# PROC099A_PMIC_Reference.net
KiCad netlist of a schematic drawn in Altium Designer
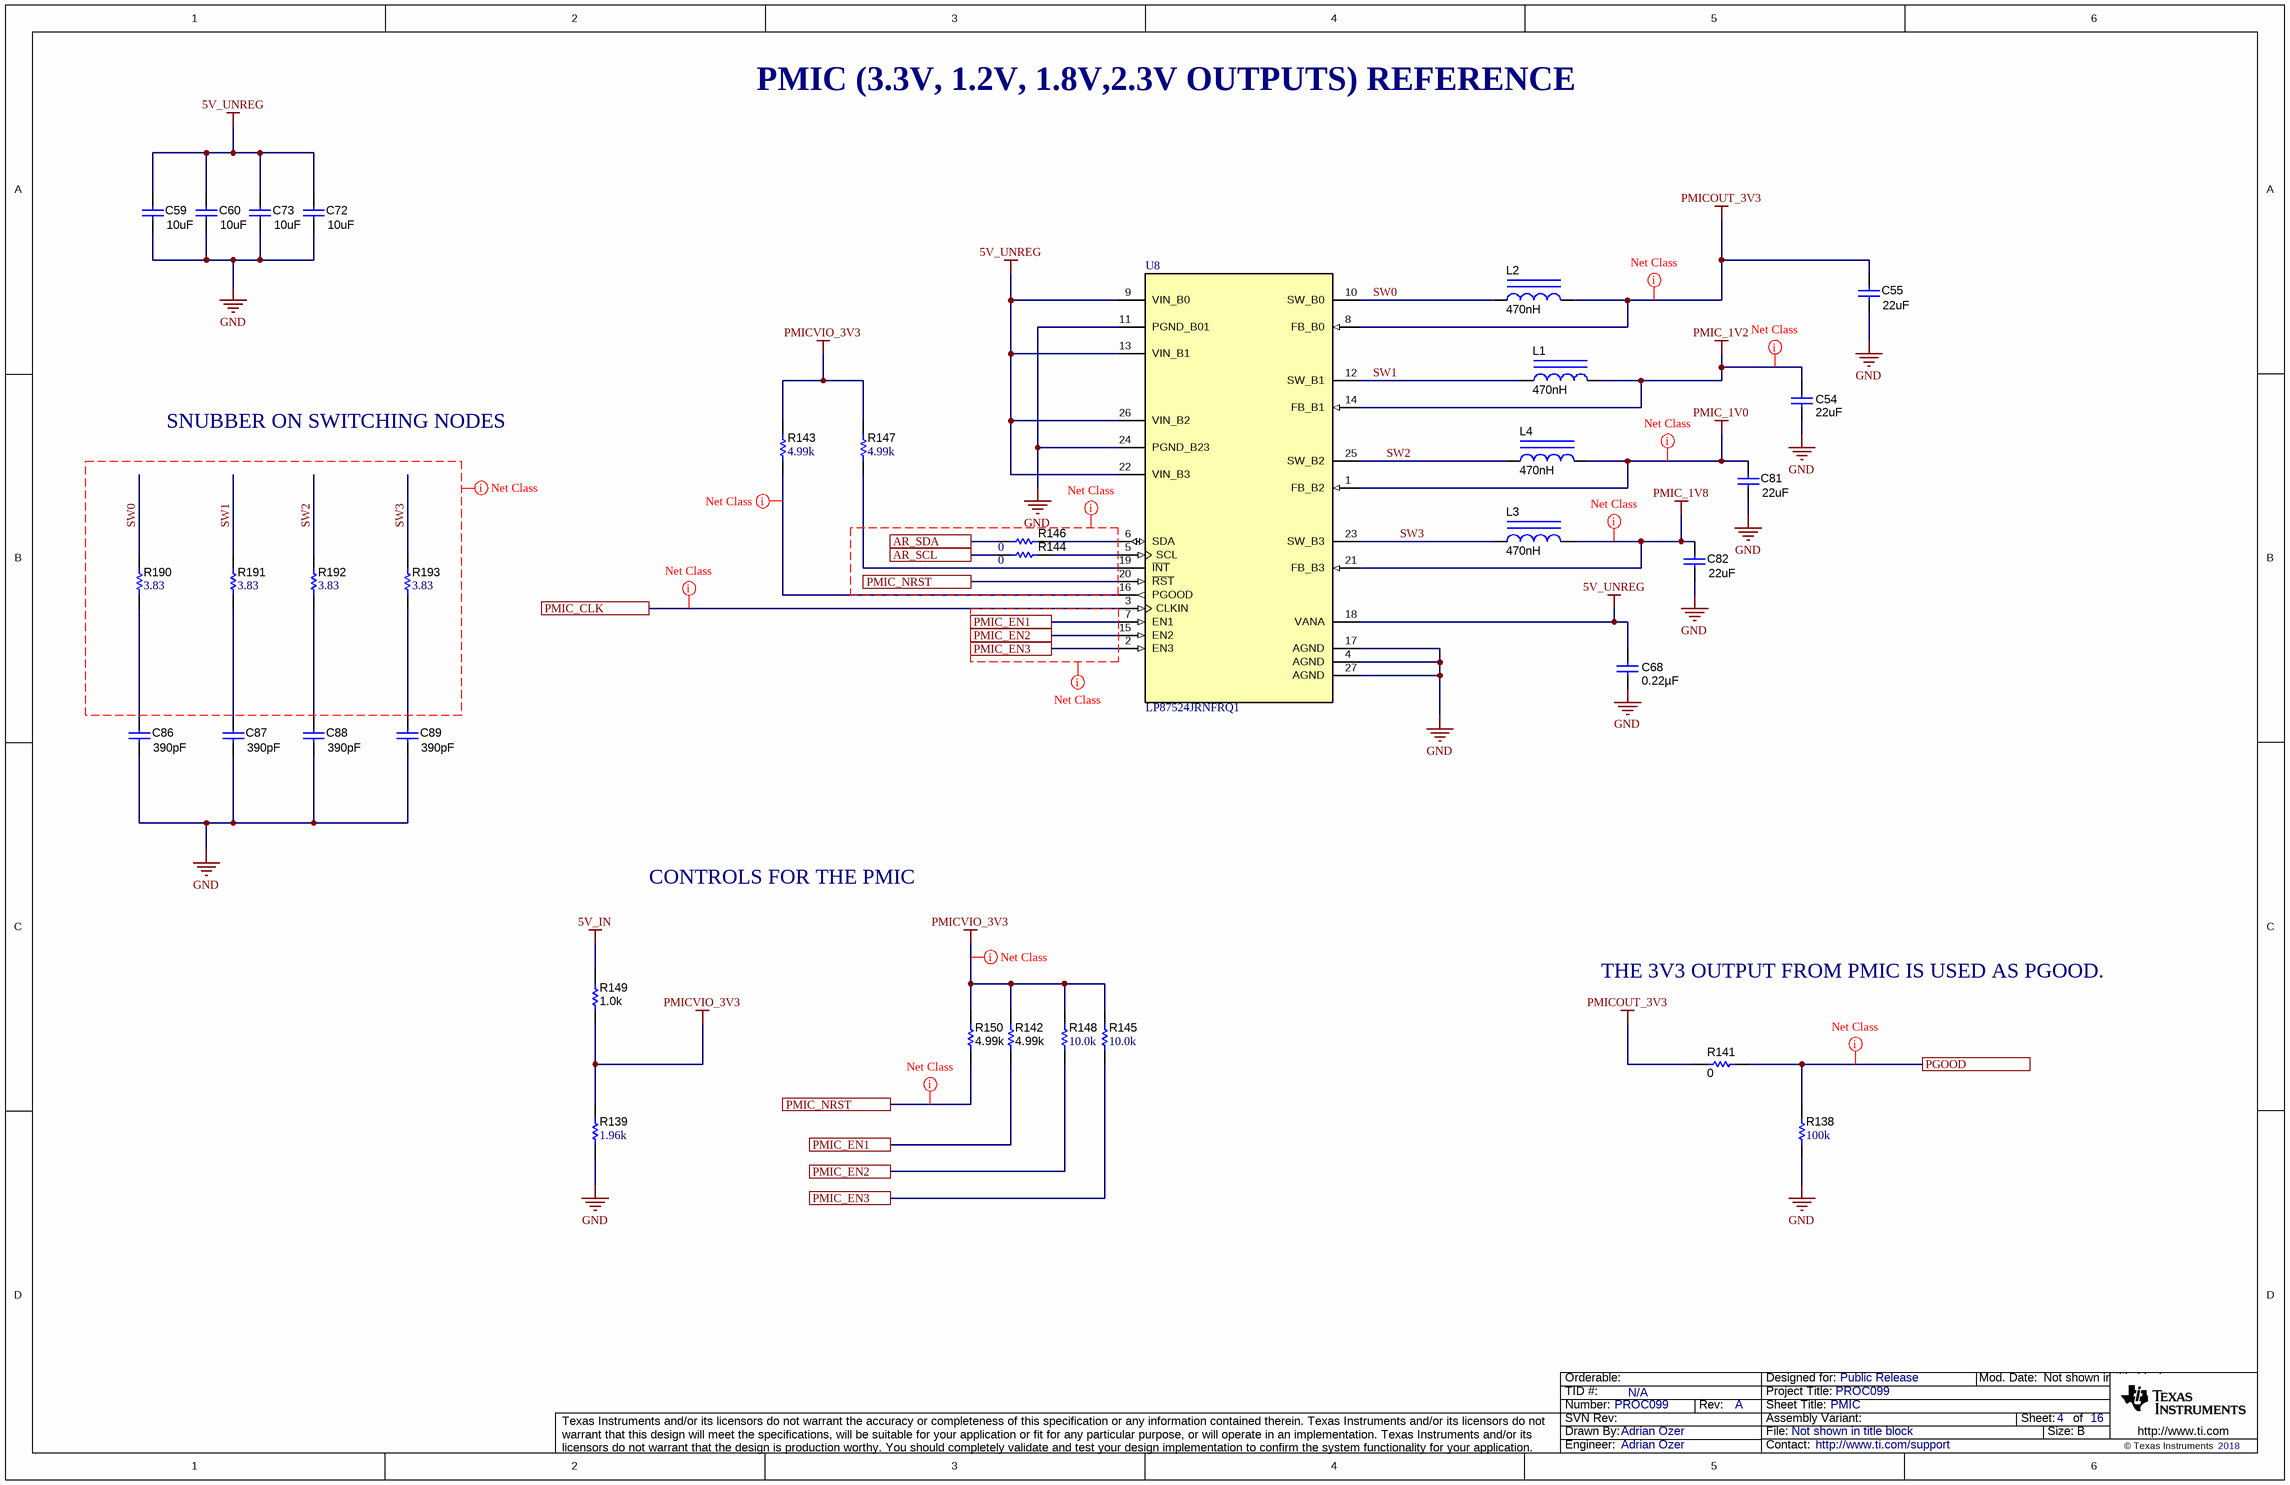
[diagram p0: PROC099A_PMIC_Reference.SchDoc]

(export (version "E")
  (design (tool "Eeschema 10.0.6"))
  (components
    (comp (ref "C54")
      (value "GCM31CR71A226KE02")
      (footprint "1206_180")
      (description "CAP, CERM, 22 uF, 10 V, +/- 10%, X7R, AEC-Q200 Grade 1, 1206")
      (fields
        (field (name "MANUFACTURER") "MuRata")
        (field (name "VALUEDISPLAYED") "22uF")
        (field (name "PUBLISHER") "Texas Instruments")
      )
      (libsource (lib "Altium Vault - TI") (part "CMP-0008811-2"))
    )
    (comp (ref "C55")
      (value "GCM31CR71A226KE02")
      (footprint "1206_180")
      (description "CAP, CERM, 22 uF, 10 V, +/- 10%, X7R, AEC-Q200 Grade 1, 1206")
      (fields
        (field (name "MANUFACTURER") "MuRata")
        (field (name "VALUEDISPLAYED") "22uF")
        (field (name "PUBLISHER") "Texas Instruments")
      )
      (libsource (lib "Altium Vault - TI") (part "Capacitor"))
    )
    (comp (ref "C59")
      (value "GCM21BR71A106KE22L")
      (footprint "0805_HV1")
      (description "CAP, CERM, 10 uF, 10 V, +/- 10%, X7R, 0805")
      (fields
        (field (name "MANUFACTURER") "MuRata")
        (field (name "VALUEDISPLAYED") "10uF")
        (field (name "PUBLISHER") "Texas Instruments")
      )
      (libsource (lib "Altium Vault - TI") (part "CMP-0008017-2"))
    )
    (comp (ref "C60")
      (value "GCM21BR71A106KE22L")
      (footprint "0805_HV1")
      (description "CAP, CERM, 10 uF, 10 V, +/- 10%, X7R, 0805")
      (fields
        (field (name "MANUFACTURER") "MuRata")
        (field (name "VALUEDISPLAYED") "10uF")
        (field (name "PUBLISHER") "Texas Instruments")
      )
      (libsource (lib "Altium Vault - TI") (part "CMP-0008017-2"))
    )
    (comp (ref "C68")
      (value "GCM155R71C224KE02D")
      (footprint "0402L")
      (description "CAP, CERM, 0.22 µF, 16 V,+/- 10%, X7R, AEC-Q200 Grade 1, 0402")
      (fields (field (name "MANUFACTURER") "MuRata") (field (name "VALUEDISPLAYED") "0.22µF"))
      (libsource (lib "Altium Vault - TI") (part "CMP-0078265-1"))
    )
    (comp (ref "C72")
      (value "GCM21BR71A106KE22L")
      (footprint "0805_HV1")
      (description "CAP, CERM, 10 uF, 10 V, +/- 10%, X7R, 0805")
      (fields
        (field (name "MANUFACTURER") "MuRata")
        (field (name "VALUEDISPLAYED") "10uF")
        (field (name "PUBLISHER") "Texas Instruments")
      )
      (libsource (lib "Altium Vault - TI") (part "CMP-0008017-2"))
    )
    (comp (ref "C73")
      (value "GCM21BR71A106KE22L")
      (footprint "0805_HV1")
      (description "CAP, CERM, 10 uF, 10 V, +/- 10%, X7R, 0805")
      (fields
        (field (name "MANUFACTURER") "MuRata")
        (field (name "VALUEDISPLAYED") "10uF")
        (field (name "PUBLISHER") "Texas Instruments")
      )
      (libsource (lib "Altium Vault - TI") (part "CMP-0008017-2"))
    )
    (comp (ref "C81")
      (value "GCM31CR71A226KE02")
      (footprint "1206_180")
      (description "CAP, CERM, 22 uF, 10 V, +/- 10%, X7R, AEC-Q200 Grade 1, 1206")
      (fields
        (field (name "MANUFACTURER") "MuRata")
        (field (name "VALUEDISPLAYED") "22uF")
        (field (name "PUBLISHER") "Texas Instruments")
      )
      (libsource (lib "Altium Vault - TI") (part "Capacitor"))
    )
    (comp (ref "C82")
      (value "GCM31CR71A226KE02")
      (footprint "1206_180")
      (description "CAP, CERM, 22 uF, 10 V, +/- 10%, X7R, AEC-Q200 Grade 1, 1206")
      (fields
        (field (name "MANUFACTURER") "MuRata")
        (field (name "VALUEDISPLAYED") "22uF")
        (field (name "PUBLISHER") "Texas Instruments")
      )
      (libsource (lib "Altium Vault - TI") (part "Capacitor"))
    )
    (comp (ref "C86")
      (value "GRM1555C1H391JA01D")
      (footprint "0402")
      (description "CAP, CERM, 390 pF, 50 V, +/- 5%, C0G/NP0, 0402")
      (fields
        (field (name "MANUFACTURER") "MuRata")
        (field (name "VALUEDISPLAYED") "390pF")
        (field (name "PUBLISHER") "Texas Instruments")
      )
      (libsource (lib "Altium Vault - TI") (part "Capacitor"))
    )
    (comp (ref "C87")
      (value "GRM1555C1H391JA01D")
      (footprint "0402")
      (description "CAP, CERM, 390 pF, 50 V, +/- 5%, C0G/NP0, 0402")
      (fields
        (field (name "MANUFACTURER") "MuRata")
        (field (name "VALUEDISPLAYED") "390pF")
        (field (name "PUBLISHER") "Texas Instruments")
      )
      (libsource (lib "Altium Vault - TI") (part "Capacitor"))
    )
    (comp (ref "C88")
      (value "GRM1555C1H391JA01D")
      (footprint "0402")
      (description "CAP, CERM, 390 pF, 50 V, +/- 5%, C0G/NP0, 0402")
      (fields
        (field (name "MANUFACTURER") "MuRata")
        (field (name "VALUEDISPLAYED") "390pF")
        (field (name "PUBLISHER") "Texas Instruments")
      )
      (libsource (lib "Altium Vault - TI") (part "Capacitor"))
    )
    (comp (ref "C89")
      (value "GRM1555C1H391JA01D")
      (footprint "0402")
      (description "CAP, CERM, 390 pF, 50 V, +/- 5%, C0G/NP0, 0402")
      (fields
        (field (name "MANUFACTURER") "MuRata")
        (field (name "VALUEDISPLAYED") "390pF")
        (field (name "PUBLISHER") "Texas Instruments")
      )
      (libsource (lib "Altium Vault - TI") (part "Capacitor"))
    )
    (comp (ref "L1")
      (value "DFE252012P-R47M=P2")
      (footprint "DFE252012P")
      (description "Inductor, Shielded, 470 nH, 4.7 A, 0.021 ohm, SMD")
      (fields
        (field (name "MANUFACTURER") "MuRata Toko")
        (field (name "VALUEDISPLAYED") "470nH")
        (field (name "PUBLISHER") "Texas Instruments")
      )
      (libsource (lib "Altium Vault - TI") (part "Inductor_Iron"))
    )
    (comp (ref "L2")
      (value "DFE252012P-R47M=P2")
      (footprint "DFE252012P")
      (description "Inductor, Shielded, 470 nH, 4.7 A, 0.021 ohm, SMD")
      (fields
        (field (name "MANUFACTURER") "MuRata Toko")
        (field (name "VALUEDISPLAYED") "470nH")
        (field (name "PUBLISHER") "Texas Instruments")
      )
      (libsource (lib "Altium Vault - TI") (part "Inductor_Iron"))
    )
    (comp (ref "L3")
      (value "DFE252012P-R47M=P2")
      (footprint "DFE252012P")
      (description "Inductor, Shielded, 470 nH, 4.7 A, 0.021 ohm, SMD")
      (fields
        (field (name "MANUFACTURER") "MuRata Toko")
        (field (name "VALUEDISPLAYED") "470nH")
        (field (name "PUBLISHER") "Texas Instruments")
      )
      (libsource (lib "Altium Vault - TI") (part "Inductor_Iron"))
    )
    (comp (ref "L4")
      (value "DFE252012P-R47M=P2")
      (footprint "DFE252012P")
      (description "Inductor, Shielded, 470 nH, 4.7 A, 0.021 ohm, SMD")
      (fields
        (field (name "MANUFACTURER") "MuRata Toko")
        (field (name "VALUEDISPLAYED") "470nH")
        (field (name "PUBLISHER") "Texas Instruments")
      )
      (libsource (lib "Altium Vault - TI") (part "Inductor_Iron"))
    )
    (comp (ref "R138")
      (value "CRCW0402100KFKED")
      (footprint "0402L")
      (description "RES, 100 k, 1%, 0.063 W, AEC-Q200 Grade 0, 0402")
      (fields (field (name "MANUFACTURER") "Vishay-Dale") (field (name "VALUEDISPLAYED") "100k"))
      (libsource (lib "Altium Vault - TI") (part "Resistor"))
    )
    (comp (ref "R139")
      (value "CRCW04021K96FKED")
      (footprint "0402L")
      (description "RES, 1.96 k, 1%, 0.063 W, AEC-Q200 Grade 0, 0402")
      (fields (field (name "MANUFACTURER") "Vishay-Dale") (field (name "VALUEDISPLAYED") "1.96k"))
      (libsource (lib "Altium Vault - TI") (part "Resistor"))
    )
    (comp (ref "R141")
      (value "ERJ-2GE0R00X")
      (footprint "0402L")
      (description "RES, 0, 5%, 0.063 W, 0402")
      (fields
        (field (name "MANUFACTURER") "Panasonic")
        (field (name "VALUEDISPLAYED") "0")
        (field (name "PUBLISHER") "Texas Instruments")
      )
      (libsource (lib "Altium Vault - TI") (part "Resistor"))
    )
    (comp (ref "R142")
      (value "ERJ-2RKF4991X")
      (footprint "0402L")
      (description "RES, 4.99 k, 1%, 0.1 W, AEC-Q200 Grade 0, 0402")
      (fields
        (field (name "MANUFACTURER") "Panasonic")
        (field (name "VALUEDISPLAYED") "4.99k")
        (field (name "PUBLISHER") "Texas Instruments")
      )
      (libsource (lib "Altium Vault - TI") (part "Resistor"))
    )
    (comp (ref "R143")
      (value "CRCW04024K99FKED")
      (footprint "0402L")
      (description "RES, 4.99 k, 1%, 0.063 W, AEC-Q200 Grade 0, 0402")
      (fields (field (name "MANUFACTURER") "Vishay-Dale") (field (name "VALUEDISPLAYED") "4.99k"))
      (libsource (lib "Altium Vault - TI") (part "Resistor"))
    )
    (comp (ref "R144")
      (value "CRCW02010000Z0ED")
      (footprint "0201_Silk")
      (description "RES, 0, 5%, 0.05 W, 0201")
      (fields (field (name "MANUFACTURER") "Vishay-Dale") (field (name "VALUEDISPLAYED") "0"))
      (libsource (lib "Altium Vault - TI") (part "Resistor"))
    )
    (comp (ref "R145")
      (value "CRCW040210K0FKED")
      (footprint "0402L")
      (description "RES, 10.0 k, 1%, 0.063 W, AEC-Q200 Grade 0, 0402")
      (fields (field (name "MANUFACTURER") "Vishay-Dale") (field (name "VALUEDISPLAYED") "10.0k"))
      (libsource (lib "Altium Vault - TI") (part "CMP-0025958-3"))
    )
    (comp (ref "R146")
      (value "CRCW02010000Z0ED")
      (footprint "0201_Silk")
      (description "RES, 0, 5%, 0.05 W, 0201")
      (fields (field (name "MANUFACTURER") "Vishay-Dale") (field (name "VALUEDISPLAYED") "0"))
      (libsource (lib "Altium Vault - TI") (part "Resistor"))
    )
    (comp (ref "R147")
      (value "CRCW04024K99FKED")
      (footprint "0402L")
      (description "RES, 4.99 k, 1%, 0.063 W, AEC-Q200 Grade 0, 0402")
      (fields (field (name "MANUFACTURER") "Vishay-Dale") (field (name "VALUEDISPLAYED") "4.99k"))
      (libsource (lib "Altium Vault - TI") (part "Resistor"))
    )
    (comp (ref "R148")
      (value "CRCW040210K0FKED")
      (footprint "0402L")
      (description "RES, 10.0 k, 1%, 0.063 W, AEC-Q200 Grade 0, 0402")
      (fields (field (name "MANUFACTURER") "Vishay-Dale") (field (name "VALUEDISPLAYED") "10.0k"))
      (libsource (lib "Altium Vault - TI") (part "Resistor"))
    )
    (comp (ref "R149")
      (value "ERJ-2GEJ102X")
      (footprint "0402L")
      (description "RES, 1.0 k, 5%, 0.1 W, AEC-Q200 Grade 0, 0402")
      (fields (field (name "MANUFACTURER") "Panasonic") (field (name "VALUEDISPLAYED") "1.0k"))
      (libsource (lib "Altium Vault - TI") (part "Resistor"))
    )
    (comp (ref "R150")
      (value "ERJ-2RKF4991X")
      (footprint "0402L")
      (description "RES, 4.99 k, 1%, 0.1 W, AEC-Q200 Grade 0, 0402")
      (fields
        (field (name "MANUFACTURER") "Panasonic")
        (field (name "VALUEDISPLAYED") "4.99k")
        (field (name "PUBLISHER") "Texas Instruments")
      )
      (libsource (lib "Altium Vault - TI") (part "Resistor"))
    )
    (comp (ref "R190")
      (value "CRCW04023R83FKED")
      (footprint "0402L")
      (description "RES, 3.83, 1%, 0.063 W, AEC-Q200 Grade 0, 0402")
      (fields (field (name "MANUFACTURER") "Vishay-Dale") (field (name "VALUEDISPLAYED") "3.83"))
      (libsource (lib "Altium Vault - TI") (part "Resistor"))
    )
    (comp (ref "R191")
      (value "CRCW04023R83FKED")
      (footprint "0402L")
      (description "RES, 3.83, 1%, 0.063 W, AEC-Q200 Grade 0, 0402")
      (fields (field (name "MANUFACTURER") "Vishay-Dale") (field (name "VALUEDISPLAYED") "3.83"))
      (libsource (lib "Altium Vault - TI") (part "Resistor"))
    )
    (comp (ref "R192")
      (value "CRCW04023R83FKED")
      (footprint "0402L")
      (description "RES, 3.83, 1%, 0.063 W, AEC-Q200 Grade 0, 0402")
      (fields (field (name "MANUFACTURER") "Vishay-Dale") (field (name "VALUEDISPLAYED") "3.83"))
      (libsource (lib "Altium Vault - TI") (part "Resistor"))
    )
    (comp (ref "R193")
      (value "CRCW04023R83FKED")
      (footprint "0402L")
      (description "RES, 3.83, 1%, 0.063 W, AEC-Q200 Grade 0, 0402")
      (fields (field (name "MANUFACTURER") "Vishay-Dale") (field (name "VALUEDISPLAYED") "3.83"))
      (libsource (lib "Altium Vault - TI") (part "Resistor"))
    )
    (comp (ref "U8")
      (value "LP87524JRNFRQ1")
      (footprint "RNF0026C")
      (description "4-A + 2.5-A + Two 1.5-A Buck Converters With Integrated Switches, RNF0026C (VQFN-HR-26)")
      (fields
        (field (name "ALTERNATE PARTNUMBER") "LP87524JRNFTQ1")
        (field (name "MANUFACTURER") "Texas Instruments")
        (field (name "PARTNUMBER") "LP87524JRNFRQ1")
      )
      (libsource (lib "Altium Vault - TI") (part "CMP-0079120-1"))
    )
  )
  (nets
    (net (code "1") (name "/AR_SCL") (class "Default")
      (node (ref "R144") (pin "1") (pinfunction "1_1") (pintype "passive"))
    )
    (net (code "2") (name "/AR_SDA") (class "Default")
      (node (ref "R146") (pin "2") (pinfunction "2_2") (pintype "passive"))
    )
    (net (code "3") (name "/PGOOD") (class "Default")
      (node (ref "R138") (pin "2") (pinfunction "2_2") (pintype "passive"))
      (node (ref "R141") (pin "2") (pinfunction "2_2") (pintype "passive"))
    )
    (net (code "4") (name "/PMIC_CLK") (class "Default")
      (node (ref "U8") (pin "3") (pinfunction "CLKIN_3") (pintype "input"))
    )
    (net (code "5") (name "/PMIC_EN1") (class "Default")
      (node (ref "R142") (pin "1") (pinfunction "1_1") (pintype "passive"))
      (node (ref "U8") (pin "7") (pinfunction "EN1_7") (pintype "input"))
    )
    (net (code "6") (name "/PMIC_EN2") (class "Default")
      (node (ref "R148") (pin "1") (pinfunction "1_1") (pintype "passive"))
      (node (ref "U8") (pin "15") (pinfunction "EN2_15") (pintype "input"))
    )
    (net (code "7") (name "/PMIC_EN3") (class "Default")
      (node (ref "R145") (pin "1") (pinfunction "1_1") (pintype "passive"))
      (node (ref "U8") (pin "2") (pinfunction "EN3_2") (pintype "input"))
    )
    (net (code "8") (name "/PMIC_NRST") (class "Default")
      (node (ref "R150") (pin "2") (pinfunction "2_2") (pintype "passive"))
      (node (ref "U8") (pin "20") (pinfunction "RST_20") (pintype "input"))
    )
    (net (code "9") (name "/SW0") (class "Default")
      (node (ref "L2") (pin "1") (pinfunction "1_1") (pintype "passive"))
      (node (ref "R190") (pin "2") (pinfunction "2_2") (pintype "passive"))
      (node (ref "U8") (pin "10") (pinfunction "SW_B0_10") (pintype "power_in"))
    )
    (net (code "10") (name "/SW1") (class "Default")
      (node (ref "L1") (pin "1") (pinfunction "1_1") (pintype "passive"))
      (node (ref "R191") (pin "2") (pinfunction "2_2") (pintype "passive"))
      (node (ref "U8") (pin "12") (pinfunction "SW_B1_12") (pintype "power_in"))
    )
    (net (code "11") (name "/SW2") (class "Default")
      (node (ref "L4") (pin "1") (pinfunction "1_1") (pintype "passive"))
      (node (ref "R192") (pin "2") (pinfunction "2_2") (pintype "passive"))
      (node (ref "U8") (pin "25") (pinfunction "SW_B2_25") (pintype "power_in"))
    )
    (net (code "12") (name "/SW3") (class "Default")
      (node (ref "L3") (pin "1") (pinfunction "1_1") (pintype "passive"))
      (node (ref "R193") (pin "2") (pinfunction "2_2") (pintype "passive"))
      (node (ref "U8") (pin "23") (pinfunction "SW_B3_23") (pintype "power_in"))
    )
    (net (code "13") (name "5V_IN") (class "Default")
      (node (ref "R149") (pin "2") (pinfunction "2_2") (pintype "passive"))
    )
    (net (code "14") (name "5V_UNREG") (class "Default")
      (node (ref "C59") (pin "2") (pinfunction "2_2") (pintype "passive"))
      (node (ref "C60") (pin "2") (pinfunction "2_2") (pintype "passive"))
      (node (ref "C68") (pin "2") (pinfunction "2_2") (pintype "passive"))
      (node (ref "C72") (pin "2") (pinfunction "2_2") (pintype "passive"))
      (node (ref "C73") (pin "2") (pinfunction "2_2") (pintype "passive"))
      (node (ref "U8") (pin "13") (pinfunction "VIN_B1_13") (pintype "power_in"))
      (node (ref "U8") (pin "18") (pinfunction "VANA_18") (pintype "power_in"))
      (node (ref "U8") (pin "22") (pinfunction "VIN_B3_22") (pintype "power_in"))
      (node (ref "U8") (pin "26") (pinfunction "VIN_B2_26") (pintype "power_in"))
      (node (ref "U8") (pin "9") (pinfunction "VIN_B0_9") (pintype "power_in"))
    )
    (net (code "15") (name "GND") (class "Default")
      (node (ref "C54") (pin "1") (pinfunction "1_1") (pintype "passive"))
      (node (ref "C55") (pin "1") (pinfunction "1_1") (pintype "passive"))
      (node (ref "C59") (pin "1") (pinfunction "1_1") (pintype "passive"))
      (node (ref "C60") (pin "1") (pinfunction "1_1") (pintype "passive"))
      (node (ref "C68") (pin "1") (pinfunction "1_1") (pintype "passive"))
      (node (ref "C72") (pin "1") (pinfunction "1_1") (pintype "passive"))
      (node (ref "C73") (pin "1") (pinfunction "1_1") (pintype "passive"))
      (node (ref "C81") (pin "1") (pinfunction "1_1") (pintype "passive"))
      (node (ref "C82") (pin "1") (pinfunction "1_1") (pintype "passive"))
      (node (ref "C86") (pin "2") (pinfunction "2_2") (pintype "passive"))
      (node (ref "C87") (pin "2") (pinfunction "2_2") (pintype "passive"))
      (node (ref "C88") (pin "2") (pinfunction "2_2") (pintype "passive"))
      (node (ref "C89") (pin "2") (pinfunction "2_2") (pintype "passive"))
      (node (ref "R138") (pin "1") (pinfunction "1_1") (pintype "passive"))
      (node (ref "R139") (pin "1") (pinfunction "1_1") (pintype "passive"))
      (node (ref "U8") (pin "11") (pinfunction "PGND_B01_11") (pintype "power_in"))
      (node (ref "U8") (pin "17") (pinfunction "AGND_17") (pintype "power_in"))
      (node (ref "U8") (pin "24") (pinfunction "PGND_B23_24") (pintype "power_in"))
      (node (ref "U8") (pin "27") (pinfunction "AGND_27") (pintype "power_in"))
      (node (ref "U8") (pin "4") (pinfunction "AGND_4") (pintype "power_in"))
    )
    (net (code "16") (name "Net-(C86-Pad1)") (class "Default")
      (node (ref "C86") (pin "1") (pinfunction "1_1") (pintype "passive"))
      (node (ref "R190") (pin "1") (pinfunction "1_1") (pintype "passive"))
    )
    (net (code "17") (name "Net-(C87-Pad1)") (class "Default")
      (node (ref "C87") (pin "1") (pinfunction "1_1") (pintype "passive"))
      (node (ref "R191") (pin "1") (pinfunction "1_1") (pintype "passive"))
    )
    (net (code "18") (name "Net-(C88-Pad1)") (class "Default")
      (node (ref "C88") (pin "1") (pinfunction "1_1") (pintype "passive"))
      (node (ref "R192") (pin "1") (pinfunction "1_1") (pintype "passive"))
    )
    (net (code "19") (name "Net-(C89-Pad1)") (class "Default")
      (node (ref "C89") (pin "1") (pinfunction "1_1") (pintype "passive"))
      (node (ref "R193") (pin "1") (pinfunction "1_1") (pintype "passive"))
    )
    (net (code "20") (name "Net-(U8-INT)") (class "Default")
      (node (ref "R147") (pin "1") (pinfunction "1_1") (pintype "passive"))
      (node (ref "U8") (pin "19") (pinfunction "INT_19") (pintype "open_collector"))
    )
    (net (code "21") (name "Net-(U8-PGOOD)") (class "Default")
      (node (ref "R143") (pin "1") (pinfunction "1_1") (pintype "passive"))
      (node (ref "U8") (pin "16") (pinfunction "PGOOD_16") (pintype "output"))
    )
    (net (code "22") (name "Net-(U8-SCL)") (class "Default")
      (node (ref "R144") (pin "2") (pinfunction "2_2") (pintype "passive"))
      (node (ref "U8") (pin "5") (pinfunction "SCL_5") (pintype "input"))
    )
    (net (code "23") (name "Net-(U8-SDA)") (class "Default")
      (node (ref "R146") (pin "1") (pinfunction "1_1") (pintype "passive"))
      (node (ref "U8") (pin "6") (pinfunction "SDA_6") (pintype "bidirectional"))
    )
    (net (code "24") (name "PMICOUT_3V3") (class "Default")
      (node (ref "C55") (pin "2") (pinfunction "2_2") (pintype "passive"))
      (node (ref "L2") (pin "2") (pinfunction "2_2") (pintype "passive"))
      (node (ref "R141") (pin "1") (pinfunction "1_1") (pintype "passive"))
      (node (ref "U8") (pin "8") (pinfunction "FB_B0_8") (pintype "input"))
    )
    (net (code "25") (name "PMICVIO_3V3") (class "Default")
      (node (ref "R139") (pin "2") (pinfunction "2_2") (pintype "passive"))
      (node (ref "R142") (pin "2") (pinfunction "2_2") (pintype "passive"))
      (node (ref "R143") (pin "2") (pinfunction "2_2") (pintype "passive"))
      (node (ref "R145") (pin "2") (pinfunction "2_2") (pintype "passive"))
      (node (ref "R147") (pin "2") (pinfunction "2_2") (pintype "passive"))
      (node (ref "R148") (pin "2") (pinfunction "2_2") (pintype "passive"))
      (node (ref "R149") (pin "1") (pinfunction "1_1") (pintype "passive"))
      (node (ref "R150") (pin "1") (pinfunction "1_1") (pintype "passive"))
    )
    (net (code "26") (name "PMIC_1V0") (class "Default")
      (node (ref "C81") (pin "2") (pinfunction "2_2") (pintype "passive"))
      (node (ref "L4") (pin "2") (pinfunction "2_2") (pintype "passive"))
      (node (ref "U8") (pin "1") (pinfunction "FB_B2_1") (pintype "input"))
    )
    (net (code "27") (name "PMIC_1V2") (class "Default")
      (node (ref "C54") (pin "2") (pinfunction "2_2") (pintype "passive"))
      (node (ref "L1") (pin "2") (pinfunction "2_2") (pintype "passive"))
      (node (ref "U8") (pin "14") (pinfunction "FB_B1_14") (pintype "input"))
    )
    (net (code "28") (name "PMIC_1V8") (class "Default")
      (node (ref "C82") (pin "2") (pinfunction "2_2") (pintype "passive"))
      (node (ref "L3") (pin "2") (pinfunction "2_2") (pintype "passive"))
      (node (ref "U8") (pin "21") (pinfunction "FB_B3_21") (pintype "input"))
    )
  )
)
